# uP.net
KiCad netlist of a schematic drawn in Altium Designer
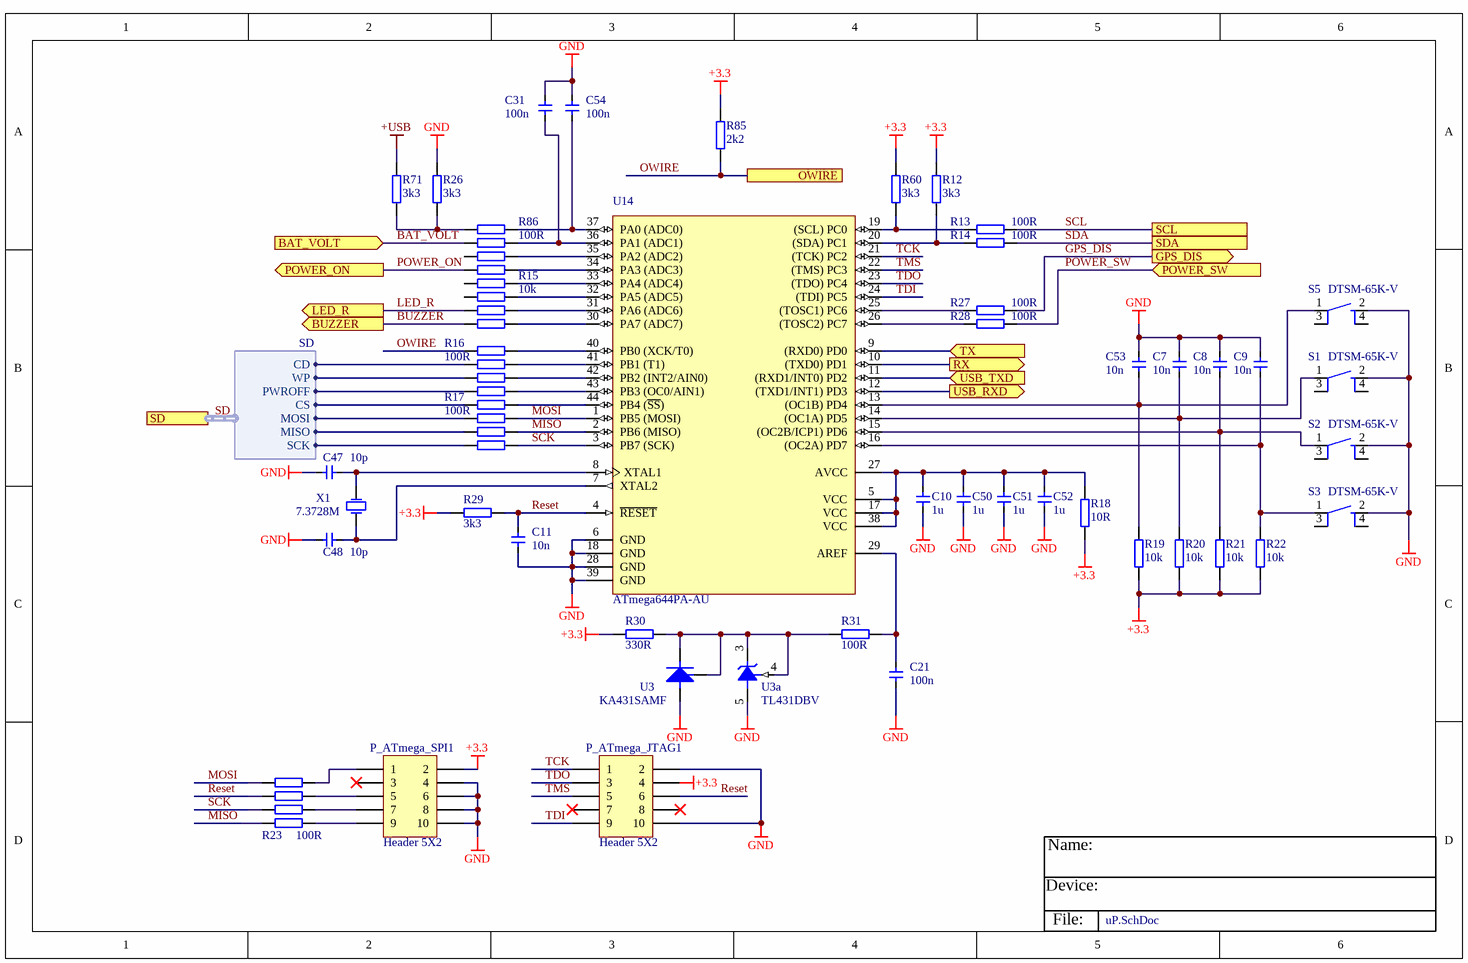
[diagram p0: uP.SchDoc]

(export (version "E")
  (design (tool "Eeschema 10.0.6"))
  (components
    (comp (ref "C7")
      (value "10n")
      (footprint "C0805")
      (description "C; capacitor")
      (libsource (lib "SONEL_all") (part "C"))
    )
    (comp (ref "C8")
      (value "10n")
      (footprint "C0805")
      (description "C; capacitor")
      (libsource (lib "SONEL_all") (part "C"))
    )
    (comp (ref "C9")
      (value "10n")
      (footprint "C0805")
      (description "C; capacitor")
      (libsource (lib "SONEL_all") (part "C"))
    )
    (comp (ref "C10")
      (value "1u")
      (footprint "C0805")
      (description "C; capacitor")
      (libsource (lib "SONEL_all") (part "C"))
    )
    (comp (ref "C11")
      (value "10n")
      (footprint "C0805")
      (description "C; capacitor")
      (libsource (lib "SONEL_all") (part "C"))
    )
    (comp (ref "C21")
      (value "100n")
      (footprint "C0805")
      (description "C; capacitor")
      (libsource (lib "SONEL_all") (part "C"))
    )
    (comp (ref "C31")
      (value "100n")
      (footprint "C0805")
      (description "C; capacitor")
      (libsource (lib "SONEL_all") (part "C"))
    )
    (comp (ref "C47")
      (value "10p")
      (footprint "C0805")
      (description "C; capacitor")
      (libsource (lib "SONEL_all") (part "C"))
    )
    (comp (ref "C48")
      (value "10p")
      (footprint "C0805")
      (description "C; capacitor")
      (libsource (lib "SONEL_all") (part "C"))
    )
    (comp (ref "C50")
      (value "1u")
      (footprint "C0805")
      (description "C; capacitor")
      (libsource (lib "SONEL_all") (part "C"))
    )
    (comp (ref "C51")
      (value "1u")
      (footprint "C0805")
      (description "C; capacitor")
      (libsource (lib "SONEL_all") (part "C"))
    )
    (comp (ref "C52")
      (value "1u")
      (footprint "C0805")
      (description "C; capacitor")
      (libsource (lib "SONEL_all") (part "C"))
    )
    (comp (ref "C53")
      (value "10n")
      (footprint "C0805")
      (description "C; capacitor")
      (libsource (lib "SONEL_all") (part "C"))
    )
    (comp (ref "C54")
      (value "100n")
      (footprint "C0805")
      (description "C; capacitor")
      (libsource (lib "SONEL_all") (part "C"))
    )
    (comp (ref "P_ATmega_JTAG1")
      (value "Header 5X2")
      (footprint "HDR2X5")
      (description "Header, 5-Pin, Dual row")
      (fields (field (name "PUBLISHER") "Altium Limited"))
      (libsource (lib "Miscellaneous Connectors") (part "Header 5X2"))
    )
    (comp (ref "P_ATmega_SPI1")
      (value "Header 5X2")
      (footprint "HDR2X5")
      (description "Header, 5-Pin, Dual row")
      (fields (field (name "PUBLISHER") "Altium Limited"))
      (libsource (lib "Miscellaneous Connectors") (part "Header 5X2"))
    )
    (comp (ref "R12")
      (value "3k3")
      (footprint "R0805")
      (description "R; resistor")
      (libsource (lib "SONEL_all") (part "R"))
    )
    (comp (ref "R13")
      (value "100R")
      (footprint "R0805")
      (description "R; resistor")
      (libsource (lib "SONEL_all") (part "R"))
    )
    (comp (ref "R14")
      (value "100R")
      (footprint "R0805")
      (description "R; resistor")
      (libsource (lib "SONEL_all") (part "R"))
    )
    (comp (ref "R15")
      (value "10k")
      (footprint "YC164")
      (description "R; Drabinka rezystorowa")
      (libsource (lib "SONEL_all") (part "YC164"))
    )
    (comp (ref "R16")
      (value "100R")
      (footprint "YC164")
      (description "R; Drabinka rezystorowa")
      (libsource (lib "SONEL_all") (part "YC164"))
    )
    (comp (ref "R17")
      (value "100R")
      (footprint "YC164")
      (description "R; Drabinka rezystorowa")
      (libsource (lib "SONEL_all") (part "YC164"))
    )
    (comp (ref "R18")
      (value "10R")
      (footprint "R0805")
      (description "R; resistor")
      (libsource (lib "SONEL_all") (part "R"))
    )
    (comp (ref "R19")
      (value "10k")
      (footprint "R0805")
      (description "R; resistor")
      (libsource (lib "SONEL_all") (part "R"))
    )
    (comp (ref "R20")
      (value "10k")
      (footprint "R0805")
      (description "R; resistor")
      (libsource (lib "SONEL_all") (part "R"))
    )
    (comp (ref "R21")
      (value "10k")
      (footprint "R0805")
      (description "R; resistor")
      (libsource (lib "SONEL_all") (part "R"))
    )
    (comp (ref "R22")
      (value "10k")
      (footprint "R0805")
      (description "R; resistor")
      (libsource (lib "SONEL_all") (part "R"))
    )
    (comp (ref "R23")
      (value "100R")
      (footprint "YC164")
      (description "R; Drabinka rezystorowa")
      (libsource (lib "SONEL_all") (part "YC164"))
    )
    (comp (ref "R26")
      (value "3k3")
      (footprint "R0805")
      (description "R; resistor")
      (libsource (lib "SONEL_all") (part "R"))
    )
    (comp (ref "R27")
      (value "100R")
      (footprint "R0805")
      (description "R; resistor")
      (libsource (lib "SONEL_all") (part "R"))
    )
    (comp (ref "R28")
      (value "100R")
      (footprint "R0805")
      (description "R; resistor")
      (libsource (lib "SONEL_all") (part "R"))
    )
    (comp (ref "R29")
      (value "3k3")
      (footprint "R0805")
      (description "R; resistor")
      (libsource (lib "SONEL_all") (part "R"))
    )
    (comp (ref "R30")
      (value "330R")
      (footprint "R0805")
      (description "R; resistor")
      (libsource (lib "SONEL_all") (part "R"))
    )
    (comp (ref "R31")
      (value "100R")
      (footprint "R0805")
      (description "R; resistor")
      (libsource (lib "SONEL_all") (part "R"))
    )
    (comp (ref "R60")
      (value "3k3")
      (footprint "R0805")
      (description "R; resistor")
      (libsource (lib "SONEL_all") (part "R"))
    )
    (comp (ref "R71")
      (value "3k3")
      (footprint "R0805")
      (description "R; resistor")
      (libsource (lib "SONEL_all") (part "R"))
    )
    (comp (ref "R85")
      (value "2k2")
      (footprint "R0805")
      (description "R; resistor")
      (libsource (lib "SONEL_all") (part "R"))
    )
    (comp (ref "R86")
      (value "100R")
      (footprint "YC164")
      (description "R; Drabinka rezystorowa")
      (libsource (lib "SONEL_all") (part "YC164"))
    )
    (comp (ref "S1")
      (value "DTSM-65K-V")
      (footprint "DTSM-65K-V")
      (description "SWITCH; TACT switch, 6x6, h=9.5mm")
      (libsource (lib "SONEL_all") (part "DTSM-65K-V"))
    )
    (comp (ref "S2")
      (value "DTSM-65K-V")
      (footprint "DTSM-65K-V")
      (description "SWITCH; TACT switch, 6x6, h=9.5mm")
      (libsource (lib "SONEL_all") (part "DTSM-65K-V"))
    )
    (comp (ref "S3")
      (value "DTSM-65K-V")
      (footprint "DTSM-65K-V")
      (description "SWITCH; TACT switch, 6x6, h=9.5mm")
      (libsource (lib "SONEL_all") (part "DTSM-65K-V"))
    )
    (comp (ref "S5")
      (value "DTSM-65K-V")
      (footprint "DTSM-65K-V")
      (description "SWITCH; TACT switch, 6x6, h=9.5mm")
      (libsource (lib "SONEL_all") (part "DTSM-65K-V"))
    )
    (comp (ref "U3")
      (value "KA431SAMF")
      (footprint "SOT23-3")
      (description "REF; SOT23; Fairchild")
      (libsource (lib "SONEL_all") (part "KA431SAMF"))
    )
    (comp (ref "U3a")
      (value "TL431DBV")
      (footprint "DBV_R-PDSO-G5")
      (description "Adjustable Precision Shunt Regulator")
      (libsource (lib "sch") (part "TL431DBV"))
    )
    (comp (ref "U14")
      (value "ATmega644PA-AU")
      (footprint "44A_M")
      (libsource (lib "SONEL_all") (part "ATmega644PA"))
    )
    (comp (ref "X1")
      (value "7.3728M")
      (footprint "HC-49SM")
      (description "OSC_Q; Crystal Oscillator")
      (libsource (lib "SONEL_all") (part "XTAL"))
    )
  )
  (nets
    (net (code "2") (name "+3.3") (class "Default")
      (node (ref "P_ATmega_JTAG1") (pin "4") (pinfunction "4_4") (pintype "passive"))
      (node (ref "P_ATmega_SPI1") (pin "2") (pinfunction "2_2") (pintype "passive"))
      (node (ref "R12") (pin "2") (pintype "passive"))
      (node (ref "R18") (pin "1") (pintype "passive"))
      (node (ref "R19") (pin "1") (pintype "passive"))
      (node (ref "R20") (pin "1") (pintype "passive"))
      (node (ref "R21") (pin "1") (pintype "passive"))
      (node (ref "R22") (pin "1") (pintype "passive"))
      (node (ref "R29") (pin "1") (pintype "passive"))
      (node (ref "R30") (pin "2") (pintype "passive"))
      (node (ref "R60") (pin "2") (pintype "passive"))
      (node (ref "R85") (pin "2") (pintype "passive"))
    )
    (net (code "3") (name "+USB") (class "Default") (node (ref "R71") (pin "2") (pintype "passive")))
    (net (code "4") (name "/BAT_VOLT") (class "Default") (node (ref "R86") (pin "3") (pintype "passive")))
    (net (code "5") (name "/BUZZER") (class "Default")
      (node (ref "R15") (pin "1") (pinfunction "1_1") (pintype "passive"))
    )
    (net (code "6") (name "/CD") (class "Default")
      (node (ref "R16") (pin "2") (pinfunction "2_2") (pintype "passive"))
    )
    (net (code "7") (name "/CS") (class "Default")
      (node (ref "R17") (pin "1") (pinfunction "1_1") (pintype "passive"))
    )
    (net (code "8") (name "/GPS_DIS") (class "Default") (node (ref "R27") (pin "1") (pintype "passive")))
    (net (code "9") (name "/LED_R") (class "Default")
      (node (ref "R15") (pin "2") (pinfunction "2_2") (pintype "passive"))
    )
    (net (code "10") (name "/MISO") (class "Default")
      (node (ref "R17") (pin "6") (pintype "passive"))
      (node (ref "R23") (pin "4") (pintype "passive"))
      (node (ref "U14") (pin "2") (pinfunction "PB6_(MISO)_2") (pintype "bidirectional"))
    )
    (net (code "11") (name "/MOSI") (class "Default")
      (node (ref "R17") (pin "7") (pintype "passive"))
      (node (ref "R23") (pin "1") (pinfunction "1_1") (pintype "passive"))
      (node (ref "U14") (pin "1") (pinfunction "PB5_(MOSI)_1") (pintype "bidirectional"))
    )
    (net (code "12") (name "/OWIRE") (class "Default")
      (node (ref "R16") (pin "1") (pinfunction "1_1") (pintype "passive"))
      (node (ref "R85") (pin "1") (pintype "passive"))
    )
    (net (code "13") (name "/POWER_ON") (class "Default")
      (node (ref "R86") (pin "1") (pinfunction "1_1") (pintype "passive"))
    )
    (net (code "14") (name "/POWER_SW") (class "Default") (node (ref "R28") (pin "1") (pintype "passive")))
    (net (code "15") (name "/PWROFF") (class "Default") (node (ref "R16") (pin "4") (pintype "passive")))
    (net (code "16") (name "/RX") (class "Default")
      (node (ref "U14") (pin "10") (pinfunction "(TXD0)_PD1_10") (pintype "bidirectional"))
    )
    (net (code "17") (name "/Reset") (class "Default")
      (node (ref "C11") (pin "2") (pintype "passive"))
      (node (ref "P_ATmega_JTAG1") (pin "6") (pinfunction "6_6") (pintype "passive"))
      (node (ref "R23") (pin "2") (pinfunction "2_2") (pintype "passive"))
      (node (ref "R29") (pin "2") (pintype "passive"))
      (node (ref "U14") (pin "4") (pinfunction "~{RESET}_4") (pintype "input"))
    )
    (net (code "18") (name "/SCK") (class "Default")
      (node (ref "R17") (pin "5") (pintype "passive"))
      (node (ref "R23") (pin "3") (pintype "passive"))
      (node (ref "U14") (pin "3") (pinfunction "PB7_(SCK)_3") (pintype "bidirectional"))
    )
    (net (code "19") (name "/SCL") (class "Default") (node (ref "R13") (pin "1") (pintype "passive")))
    (net (code "20") (name "/SDA") (class "Default") (node (ref "R14") (pin "1") (pintype "passive")))
    (net (code "22") (name "/TCK") (class "Default")
      (node (ref "P_ATmega_JTAG1") (pin "1") (pinfunction "1_1") (pintype "passive"))
      (node (ref "U14") (pin "21") (pinfunction "(TCK)_PC2_21") (pintype "bidirectional"))
    )
    (net (code "23") (name "/TDI") (class "Default")
      (node (ref "P_ATmega_JTAG1") (pin "9") (pinfunction "9_9") (pintype "passive"))
      (node (ref "U14") (pin "24") (pinfunction "(TDI)_PC5_24") (pintype "bidirectional"))
    )
    (net (code "24") (name "/TDO") (class "Default")
      (node (ref "P_ATmega_JTAG1") (pin "3") (pinfunction "3_3") (pintype "passive"))
      (node (ref "U14") (pin "23") (pinfunction "(TDO)_PC4_23") (pintype "bidirectional"))
    )
    (net (code "25") (name "/TMS") (class "Default")
      (node (ref "P_ATmega_JTAG1") (pin "5") (pinfunction "5_5") (pintype "passive"))
      (node (ref "U14") (pin "22") (pinfunction "(TMS)_PC3_22") (pintype "bidirectional"))
    )
    (net (code "26") (name "/TX") (class "Default")
      (node (ref "U14") (pin "9") (pinfunction "(RXD0)_PD0_9") (pintype "bidirectional"))
    )
    (net (code "27") (name "/USB_RXD") (class "Default")
      (node (ref "U14") (pin "12") (pinfunction "(TXD1/INT1)_PD3_12") (pintype "bidirectional"))
    )
    (net (code "28") (name "/USB_TXD") (class "Default")
      (node (ref "U14") (pin "11") (pinfunction "(RXD1/INT0)_PD2_11") (pintype "bidirectional"))
    )
    (net (code "29") (name "/WP") (class "Default") (node (ref "R16") (pin "3") (pintype "passive")))
    (net (code "30") (name "GND") (class "Default")
      (node (ref "C10") (pin "1") (pintype "passive"))
      (node (ref "C11") (pin "1") (pintype "passive"))
      (node (ref "C21") (pin "1") (pintype "passive"))
      (node (ref "C31") (pin "2") (pintype "passive"))
      (node (ref "C47") (pin "1") (pintype "passive"))
      (node (ref "C48") (pin "1") (pintype "passive"))
      (node (ref "C50") (pin "1") (pintype "passive"))
      (node (ref "C51") (pin "1") (pintype "passive"))
      (node (ref "C52") (pin "1") (pintype "passive"))
      (node (ref "C53") (pin "2") (pintype "passive"))
      (node (ref "C54") (pin "2") (pintype "passive"))
      (node (ref "C7") (pin "2") (pintype "passive"))
      (node (ref "C8") (pin "2") (pintype "passive"))
      (node (ref "C9") (pin "2") (pintype "passive"))
      (node (ref "P_ATmega_JTAG1") (pin "10") (pinfunction "10_10") (pintype "passive"))
      (node (ref "P_ATmega_JTAG1") (pin "2") (pinfunction "2_2") (pintype "passive"))
      (node (ref "P_ATmega_SPI1") (pin "10") (pinfunction "10_10") (pintype "passive"))
      (node (ref "P_ATmega_SPI1") (pin "4") (pinfunction "4_4") (pintype "passive"))
      (node (ref "P_ATmega_SPI1") (pin "6") (pinfunction "6_6") (pintype "passive"))
      (node (ref "P_ATmega_SPI1") (pin "8") (pinfunction "8_8") (pintype "passive"))
      (node (ref "R26") (pin "2") (pintype "passive"))
      (node (ref "S1") (pin "2") (pinfunction "S1_2") (pintype "passive"))
      (node (ref "S2") (pin "2") (pinfunction "S1_2") (pintype "passive"))
      (node (ref "S3") (pin "2") (pinfunction "S1_2") (pintype "passive"))
      (node (ref "S5") (pin "2") (pinfunction "S1_2") (pintype "passive"))
      (node (ref "U14") (pin "18") (pinfunction "GND_18") (pintype "power_in"))
      (node (ref "U14") (pin "28") (pinfunction "GND_28") (pintype "power_in"))
      (node (ref "U14") (pin "39") (pinfunction "GND_39") (pintype "power_in"))
      (node (ref "U14") (pin "6") (pinfunction "GND_6") (pintype "power_in"))
      (node (ref "U3") (pin "3") (pinfunction "A_3") (pintype "passive"))
      (node (ref "U3a") (pin "5") (pinfunction "A_5") (pintype "passive"))
    )
    (net (code "31") (name "Net-(P_ATmega_SPI1-Pad1)") (class "Default")
      (node (ref "P_ATmega_SPI1") (pin "1") (pinfunction "1_1") (pintype "passive"))
      (node (ref "R23") (pin "8") (pintype "passive"))
    )
    (net (code "32") (name "Net-(P_ATmega_SPI1-Pad5)") (class "Default")
      (node (ref "P_ATmega_SPI1") (pin "5") (pinfunction "5_5") (pintype "passive"))
      (node (ref "R23") (pin "7") (pintype "passive"))
    )
    (net (code "33") (name "Net-(P_ATmega_SPI1-Pad7)") (class "Default")
      (node (ref "P_ATmega_SPI1") (pin "7") (pinfunction "7_7") (pintype "passive"))
      (node (ref "R23") (pin "6") (pintype "passive"))
    )
    (net (code "34") (name "Net-(P_ATmega_SPI1-Pad9)") (class "Default")
      (node (ref "P_ATmega_SPI1") (pin "9") (pinfunction "9_9") (pintype "passive"))
      (node (ref "R23") (pin "5") (pintype "passive"))
    )
    (net (code "35") (name "Net-(R26-Pad1)") (class "Default")
      (node (ref "R26") (pin "1") (pintype "passive"))
      (node (ref "R71") (pin "1") (pintype "passive"))
      (node (ref "R86") (pin "4") (pintype "passive"))
    )
    (net (code "36") (name "Net-(S1-P1)") (class "Default")
      (node (ref "C7") (pin "1") (pintype "passive"))
      (node (ref "R20") (pin "2") (pintype "passive"))
      (node (ref "S1") (pin "1") (pinfunction "P1_1") (pintype "passive"))
      (node (ref "U14") (pin "14") (pinfunction "(OC1A)_PD5_14") (pintype "bidirectional"))
    )
    (net (code "37") (name "Net-(S2-P1)") (class "Default")
      (node (ref "C8") (pin "1") (pintype "passive"))
      (node (ref "R21") (pin "2") (pintype "passive"))
      (node (ref "S2") (pin "1") (pinfunction "P1_1") (pintype "passive"))
      (node (ref "U14") (pin "15") (pinfunction "(OC2B/ICP1)_PD6_15") (pintype "bidirectional"))
    )
    (net (code "38") (name "Net-(S3-P1)") (class "Default")
      (node (ref "C9") (pin "1") (pintype "passive"))
      (node (ref "R22") (pin "2") (pintype "passive"))
      (node (ref "S3") (pin "1") (pinfunction "P1_1") (pintype "passive"))
      (node (ref "U14") (pin "16") (pinfunction "(OC2A)_PD7_16") (pintype "bidirectional"))
    )
    (net (code "39") (name "Net-(S5-P1)") (class "Default")
      (node (ref "C53") (pin "1") (pintype "passive"))
      (node (ref "R19") (pin "2") (pintype "passive"))
      (node (ref "S5") (pin "1") (pinfunction "P1_1") (pintype "passive"))
      (node (ref "U14") (pin "13") (pinfunction "(OC1B)_PD4_13") (pintype "bidirectional"))
    )
    (net (code "40") (name "Net-(U3-K)") (class "Default")
      (node (ref "R30") (pin "1") (pintype "passive"))
      (node (ref "R31") (pin "2") (pintype "passive"))
      (node (ref "U3") (pin "1") (pinfunction "K_1") (pintype "passive"))
      (node (ref "U3") (pin "2") (pinfunction "R_2") (pintype "passive"))
      (node (ref "U3a") (pin "3") (pinfunction "K_3") (pintype "passive"))
      (node (ref "U3a") (pin "4") (pinfunction "REF_4") (pintype "input"))
    )
    (net (code "41") (name "Net-(U14-(SCL)_PC0)") (class "Default")
      (node (ref "R13") (pin "2") (pintype "passive"))
      (node (ref "R60") (pin "1") (pintype "passive"))
      (node (ref "U14") (pin "19") (pinfunction "(SCL)_PC0_19") (pintype "bidirectional"))
    )
    (net (code "42") (name "Net-(U14-(SDA)_PC1)") (class "Default")
      (node (ref "R12") (pin "1") (pintype "passive"))
      (node (ref "R14") (pin "2") (pintype "passive"))
      (node (ref "U14") (pin "20") (pinfunction "(SDA)_PC1_20") (pintype "bidirectional"))
    )
    (net (code "43") (name "Net-(U14-(TOSC1)_PC6)") (class "Default")
      (node (ref "R27") (pin "2") (pintype "passive"))
      (node (ref "U14") (pin "25") (pinfunction "(TOSC1)_PC6_25") (pintype "bidirectional"))
    )
    (net (code "44") (name "Net-(U14-(TOSC2)_PC7)") (class "Default")
      (node (ref "R28") (pin "2") (pintype "passive"))
      (node (ref "U14") (pin "26") (pinfunction "(TOSC2)_PC7_26") (pintype "bidirectional"))
    )
    (net (code "45") (name "Net-(U14-AREF)") (class "Default")
      (node (ref "C21") (pin "2") (pintype "passive"))
      (node (ref "R31") (pin "1") (pintype "passive"))
      (node (ref "U14") (pin "29") (pinfunction "AREF_29") (pintype "power_in"))
    )
    (net (code "46") (name "Net-(U14-AVCC)") (class "Default")
      (node (ref "C10") (pin "2") (pintype "passive"))
      (node (ref "C50") (pin "2") (pintype "passive"))
      (node (ref "C51") (pin "2") (pintype "passive"))
      (node (ref "C52") (pin "2") (pintype "passive"))
      (node (ref "R18") (pin "2") (pintype "passive"))
      (node (ref "U14") (pin "17") (pinfunction "VCC_17") (pintype "power_in"))
      (node (ref "U14") (pin "27") (pinfunction "AVCC_27") (pintype "power_in"))
      (node (ref "U14") (pin "38") (pinfunction "VCC_38") (pintype "power_in"))
      (node (ref "U14") (pin "5") (pinfunction "VCC_5") (pintype "power_in"))
    )
    (net (code "47") (name "Net-(U14-PA0_(ADC0))") (class "Default")
      (node (ref "C54") (pin "1") (pintype "passive"))
      (node (ref "R86") (pin "5") (pintype "passive"))
      (node (ref "U14") (pin "37") (pinfunction "PA0_(ADC0)_37") (pintype "bidirectional"))
    )
    (net (code "48") (name "Net-(U14-PA1_(ADC1))") (class "Default")
      (node (ref "C31") (pin "1") (pintype "passive"))
      (node (ref "R86") (pin "6") (pintype "passive"))
      (node (ref "U14") (pin "36") (pinfunction "PA1_(ADC1)_36") (pintype "bidirectional"))
    )
    (net (code "49") (name "Net-(U14-PA2_(ADC2))") (class "Default")
      (node (ref "R86") (pin "7") (pintype "passive"))
      (node (ref "U14") (pin "35") (pinfunction "PA2_(ADC2)_35") (pintype "bidirectional"))
    )
    (net (code "50") (name "Net-(U14-PA3_(ADC3))") (class "Default")
      (node (ref "R86") (pin "8") (pintype "passive"))
      (node (ref "U14") (pin "34") (pinfunction "PA3_(ADC3)_34") (pintype "bidirectional"))
    )
    (net (code "51") (name "Net-(U14-PA4_(ADC4))") (class "Default")
      (node (ref "R15") (pin "5") (pintype "passive"))
      (node (ref "U14") (pin "33") (pinfunction "PA4_(ADC4)_33") (pintype "bidirectional"))
    )
    (net (code "52") (name "Net-(U14-PA5_(ADC5))") (class "Default")
      (node (ref "R15") (pin "6") (pintype "passive"))
      (node (ref "U14") (pin "32") (pinfunction "PA5_(ADC5)_32") (pintype "bidirectional"))
    )
    (net (code "53") (name "Net-(U14-PA6_(ADC6))") (class "Default")
      (node (ref "R15") (pin "7") (pintype "passive"))
      (node (ref "U14") (pin "31") (pinfunction "PA6_(ADC6)_31") (pintype "bidirectional"))
    )
    (net (code "54") (name "Net-(U14-PA7_(ADC7))") (class "Default")
      (node (ref "R15") (pin "8") (pintype "passive"))
      (node (ref "U14") (pin "30") (pinfunction "PA7_(ADC7)_30") (pintype "bidirectional"))
    )
    (net (code "55") (name "Net-(U14-PB0_(XCK{slash}T0))") (class "Default")
      (node (ref "R16") (pin "8") (pintype "passive"))
      (node (ref "U14") (pin "40") (pinfunction "PB0_(XCK/T0)_40") (pintype "bidirectional"))
    )
    (net (code "56") (name "Net-(U14-PB1_(T1))") (class "Default")
      (node (ref "R16") (pin "7") (pintype "passive"))
      (node (ref "U14") (pin "41") (pinfunction "PB1_(T1)_41") (pintype "bidirectional"))
    )
    (net (code "57") (name "Net-(U14-PB2_(INT2{slash}AIN0))") (class "Default")
      (node (ref "R16") (pin "6") (pintype "passive"))
      (node (ref "U14") (pin "42") (pinfunction "PB2_(INT2/AIN0)_42") (pintype "bidirectional"))
    )
    (net (code "58") (name "Net-(U14-PB3_(OC0{slash}AIN1))") (class "Default")
      (node (ref "R16") (pin "5") (pintype "passive"))
      (node (ref "U14") (pin "43") (pinfunction "PB3_(OC0/AIN1)_43") (pintype "bidirectional"))
    )
    (net (code "59") (name "Net-(U14-PB4_(~{SS}))") (class "Default")
      (node (ref "R17") (pin "8") (pintype "passive"))
      (node (ref "U14") (pin "44") (pinfunction "PB4_(~{SS})_44") (pintype "bidirectional"))
    )
    (net (code "60") (name "Net-(U14-XTAL1)") (class "Default")
      (node (ref "C47") (pin "2") (pintype "passive"))
      (node (ref "U14") (pin "8") (pinfunction "XTAL1_8") (pintype "input"))
      (node (ref "X1") (pin "2") (pinfunction "OSC2_2") (pintype "passive"))
    )
    (net (code "61") (name "Net-(U14-XTAL2)") (class "Default")
      (node (ref "C48") (pin "2") (pintype "passive"))
      (node (ref "U14") (pin "7") (pinfunction "XTAL2_7") (pintype "output"))
      (node (ref "X1") (pin "1") (pinfunction "OSC1_1") (pintype "passive"))
    )
    (net (code "62") (name "unconnected-(P_ATmega_JTAG1-Pad7)") (class "Default")
      (node (ref "P_ATmega_JTAG1") (pin "7") (pinfunction "7_7") (pintype "passive+no_connect"))
    )
    (net (code "63") (name "unconnected-(P_ATmega_JTAG1-Pad8)") (class "Default")
      (node (ref "P_ATmega_JTAG1") (pin "8") (pinfunction "8_8") (pintype "passive+no_connect"))
    )
    (net (code "64") (name "unconnected-(P_ATmega_SPI1-Pad3)") (class "Default")
      (node (ref "P_ATmega_SPI1") (pin "3") (pinfunction "3_3") (pintype "passive+no_connect"))
    )
    (net (code "65") (name "unconnected-(R15-Pad3)") (class "Default")
      (node (ref "R15") (pin "3") (pintype "passive"))
    )
    (net (code "66") (name "unconnected-(R15-Pad4)") (class "Default")
      (node (ref "R15") (pin "4") (pintype "passive"))
    )
    (net (code "67") (name "unconnected-(R17-Pad2)") (class "Default")
      (node (ref "R17") (pin "2") (pinfunction "2_2") (pintype "passive"))
    )
    (net (code "68") (name "unconnected-(R17-Pad3)") (class "Default")
      (node (ref "R17") (pin "3") (pintype "passive"))
    )
    (net (code "69") (name "unconnected-(R17-Pad4)") (class "Default")
      (node (ref "R17") (pin "4") (pintype "passive"))
    )
    (net (code "70") (name "unconnected-(R86-Pad2)") (class "Default")
      (node (ref "R86") (pin "2") (pinfunction "2_2") (pintype "passive"))
    )
    (net (code "71") (name "unconnected-(S1-2-Pad4)") (class "Default")
      (node (ref "S1") (pin "4") (pinfunction "2_4") (pintype "passive"))
    )
    (net (code "72") (name "unconnected-(S1-P2-Pad3)") (class "Default")
      (node (ref "S1") (pin "3") (pinfunction "P2_3") (pintype "passive"))
    )
    (net (code "73") (name "unconnected-(S2-2-Pad4)") (class "Default")
      (node (ref "S2") (pin "4") (pinfunction "2_4") (pintype "passive"))
    )
    (net (code "74") (name "unconnected-(S2-P2-Pad3)") (class "Default")
      (node (ref "S2") (pin "3") (pinfunction "P2_3") (pintype "passive"))
    )
    (net (code "75") (name "unconnected-(S3-2-Pad4)") (class "Default")
      (node (ref "S3") (pin "4") (pinfunction "2_4") (pintype "passive"))
    )
    (net (code "76") (name "unconnected-(S3-P2-Pad3)") (class "Default")
      (node (ref "S3") (pin "3") (pinfunction "P2_3") (pintype "passive"))
    )
    (net (code "77") (name "unconnected-(S5-2-Pad4)") (class "Default")
      (node (ref "S5") (pin "4") (pinfunction "2_4") (pintype "passive"))
    )
    (net (code "78") (name "unconnected-(S5-P2-Pad3)") (class "Default")
      (node (ref "S5") (pin "3") (pinfunction "P2_3") (pintype "passive"))
    )
  )
)
